# 04_AudioCodec.net
KiCad netlist of a schematic drawn in Altium Designer
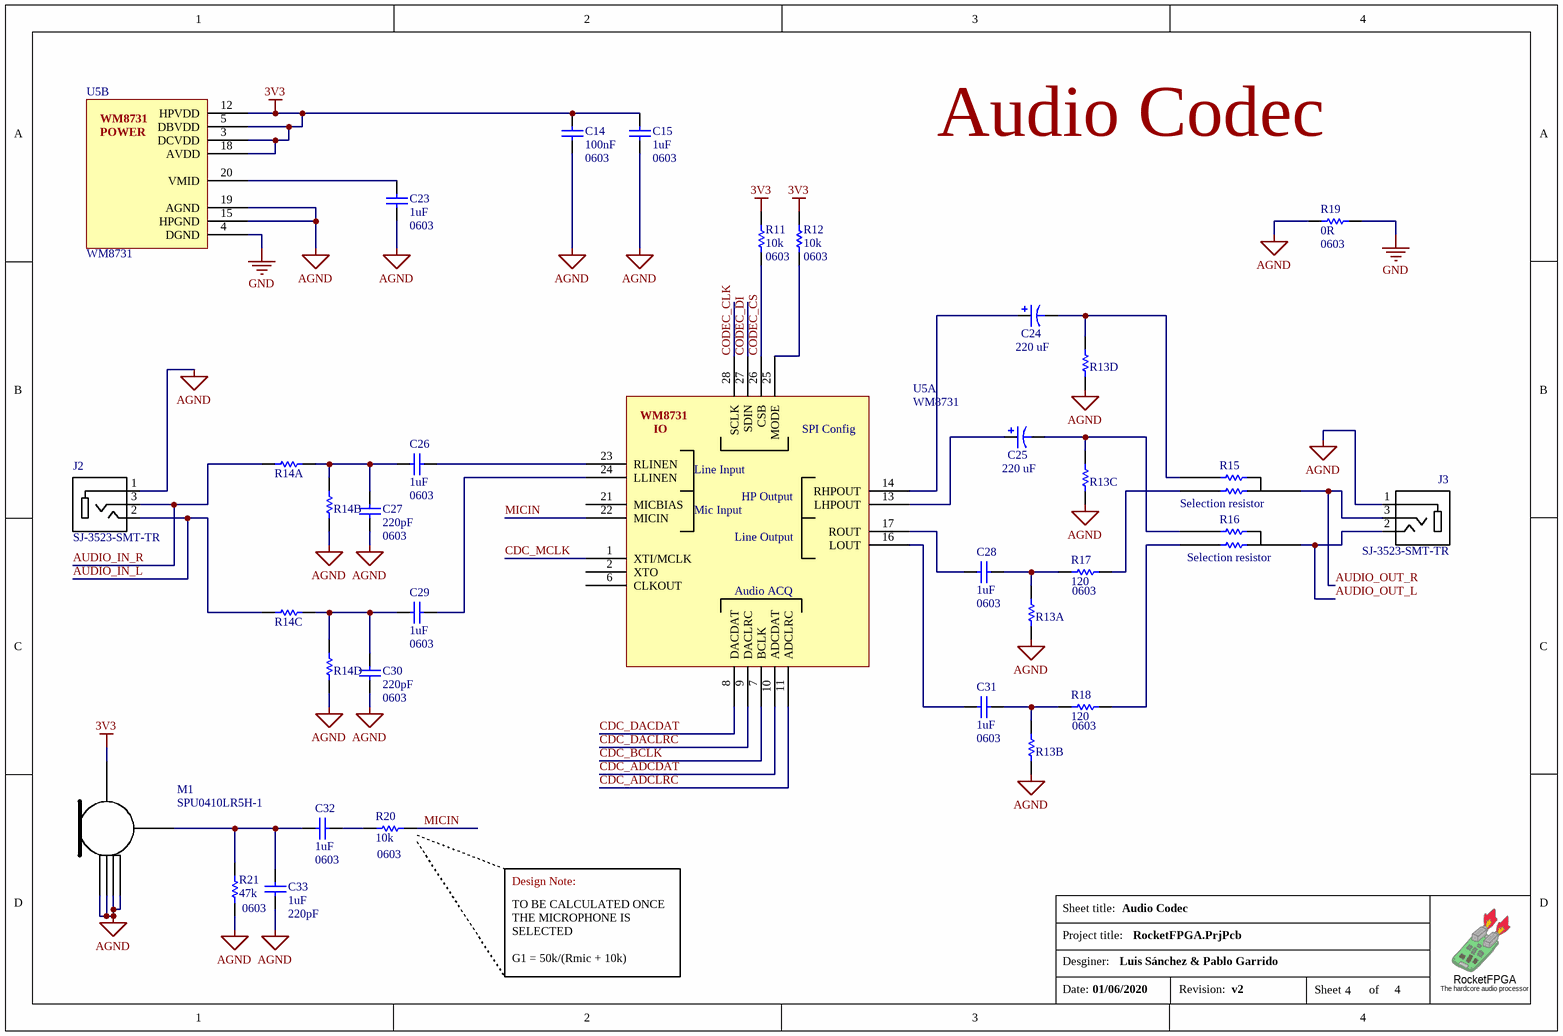
[diagram p0: 04_AudioCodec.SchDoc]

(export (version "E")
  (design (tool "Eeschema 10.0.6"))
  (components
    (comp (ref "C14")
      (value "100nF")
      (footprint "0603 CAP")
      (description "Capacitor")
      (fields (field (name "PACKAGE") "0603") (field (name "Comment") "Ceramic capacitor"))
      (libsource (lib "RocketFPGA") (part "Capacitor"))
    )
    (comp (ref "C15")
      (value "1uF")
      (footprint "0603 CAP")
      (description "Capacitor")
      (fields (field (name "PACKAGE") "0603") (field (name "Comment") "Ceramic capacitor"))
      (libsource (lib "RocketFPGA") (part "Capacitor"))
    )
    (comp (ref "C23")
      (value "1uF")
      (footprint "0603 CAP")
      (description "Capacitor")
      (fields (field (name "PACKAGE") "0603") (field (name "Comment") "Ceramic capacitor"))
      (libsource (lib "RocketFPGA") (part "Capacitor"))
    )
    (comp (ref "C24")
      (value "220 uF")
      (footprint "CAPCP3216X16N")
      (description "Capacitor Electrolitic")
      (fields (field (name "AUTHOR") "Jaime Jiménez Ortega"))
      (libsource (lib "RocketFPGA") (part "Capacitor Electrolitic"))
    )
    (comp (ref "C25")
      (value "220 uF")
      (footprint "CAPCP3216X16N")
      (description "Capacitor Electrolitic")
      (fields (field (name "AUTHOR") "Jaime Jiménez Ortega"))
      (libsource (lib "RocketFPGA") (part "Capacitor Electrolitic"))
    )
    (comp (ref "C26")
      (value "1uF")
      (footprint "0603 CAP")
      (description "Capacitor")
      (fields (field (name "PACKAGE") "0603") (field (name "Comment") "Ceramic capacitor"))
      (libsource (lib "RocketFPGA") (part "Capacitor"))
    )
    (comp (ref "C27")
      (value "220pF")
      (footprint "0603 CAP")
      (description "Capacitor")
      (fields (field (name "PACKAGE") "0603") (field (name "Comment") "Ceramic capacitor"))
      (libsource (lib "RocketFPGA") (part "Capacitor"))
    )
    (comp (ref "C28")
      (value "1uF")
      (footprint "0603 CAP")
      (description "Capacitor")
      (fields (field (name "PACKAGE") "0603") (field (name "Comment") "Ceramic capacitor"))
      (libsource (lib "RocketFPGA") (part "Capacitor"))
    )
    (comp (ref "C29")
      (value "1uF")
      (footprint "0603 CAP")
      (description "Capacitor")
      (fields (field (name "PACKAGE") "0603") (field (name "Comment") "Ceramic capacitor"))
      (libsource (lib "RocketFPGA") (part "Capacitor"))
    )
    (comp (ref "C30")
      (value "220pF")
      (footprint "0603 CAP")
      (description "Capacitor")
      (fields (field (name "PACKAGE") "0603") (field (name "Comment") "Ceramic capacitor"))
      (libsource (lib "RocketFPGA") (part "Capacitor"))
    )
    (comp (ref "C31")
      (value "1uF")
      (footprint "0603 CAP")
      (description "Capacitor")
      (fields (field (name "PACKAGE") "0603") (field (name "Comment") "Ceramic capacitor"))
      (libsource (lib "RocketFPGA") (part "Capacitor"))
    )
    (comp (ref "C32")
      (value "1uF")
      (footprint "0603 CAP")
      (description "Capacitor")
      (fields (field (name "PACKAGE") "0603") (field (name "Comment") "Ceramic capacitor"))
      (libsource (lib "RocketFPGA") (part "Capacitor"))
    )
    (comp (ref "C33")
      (value "1uF")
      (footprint "0603 CAP")
      (description "Capacitor")
      (fields (field (name "PACKAGE") "220pF") (field (name "Comment") "Ceramic capacitor"))
      (libsource (lib "RocketFPGA") (part "Capacitor"))
    )
    (comp (ref "J2")
      (value "SJ-3523-SMT-TR")
      (footprint "CUI_SJ-3523-SMT-TR")
      (description "Jack connector")
      (libsource (lib "RocketFPGA") (part "SJ-3523-SMT-TR"))
    )
    (comp (ref "J3")
      (value "SJ-3523-SMT-TR")
      (footprint "CUI_SJ-3523-SMT-TR")
      (libsource (lib "RocketFPGA") (part "SJ-3523-SMT-TR"))
    )
    (comp (ref "M1")
      (value "SPU0410LR5H-1")
      (footprint "SPU0410LR5H-1")
      (description "MEMS Microphone")
      (libsource (lib "RocketFPGA") (part "SPU0410LR5H-1"))
    )
    (comp (ref "R11")
      (value "10k")
      (footprint "Resistencia 0603")
      (description "Resistor")
      (fields (field (name "PACKAGE") "0603"))
      (libsource (lib "RocketFPGA") (part "Resistor"))
    )
    (comp (ref "R12")
      (value "10k")
      (footprint "Resistencia 0603")
      (description "Resistor")
      (fields (field (name "PACKAGE") "0603"))
      (libsource (lib "RocketFPGA") (part "Resistor"))
    )
    (comp (ref "R13")
      (value "Resistor array")
      (description "4 resistors in smd array configuration")
      (libsource (lib "RocketFPGA") (part "ResistorArray_4"))
    )
    (comp (ref "R14")
      (value "Resistor array")
      (description "4 resistors in smd array configuration")
      (libsource (lib "RocketFPGA") (part "ResistorArray_4"))
    )
    (comp (ref "R15") (value "Selection resistor") (libsource (lib "RocketFPGA") (part "SelectionResistor")))
    (comp (ref "R16") (value "Selection resistor") (libsource (lib "RocketFPGA") (part "SelectionResistor")))
    (comp (ref "R17")
      (value "120")
      (footprint "Resistencia 0603")
      (description "Resistor")
      (fields (field (name "PACKAGE") "0603"))
      (libsource (lib "RocketFPGA") (part "Resistor"))
    )
    (comp (ref "R18")
      (value "120")
      (footprint "Resistencia 0603")
      (description "Resistor")
      (fields (field (name "PACKAGE") "0603"))
      (libsource (lib "RocketFPGA") (part "Resistor"))
    )
    (comp (ref "R19")
      (value "0R")
      (footprint "Resistencia 0603")
      (description "Resistor")
      (fields (field (name "PACKAGE") "0603"))
      (libsource (lib "RocketFPGA") (part "Resistor"))
    )
    (comp (ref "R20")
      (value "10k")
      (footprint "Resistencia 0603")
      (description "Resistor")
      (fields (field (name "PACKAGE") "0603"))
      (libsource (lib "RocketFPGA") (part "Resistor"))
    )
    (comp (ref "R21")
      (value "47k")
      (footprint "Resistencia 0603")
      (description "Resistor")
      (fields (field (name "PACKAGE") "0603"))
      (libsource (lib "RocketFPGA") (part "Resistor"))
    )
    (comp (ref "U5")
      (value "WM8731")
      (footprint "WM8731")
      (description "Portable Internet Audio CODEC with Headphone Driver  and Programmable Sample Rates")
      (libsource (lib "RocketFPGA") (part "WM8731"))
    )
  )
  (nets
    (net (code "1") (name "/AUDIO_IN_L") (class "Default")
      (node (ref "J2") (pin "2") (pinfunction "2_2") (pintype "passive"))
      (node (ref "R14") (pin "3") (pinfunction "3_3") (pintype "passive"))
    )
    (net (code "2") (name "/AUDIO_IN_R") (class "Default")
      (node (ref "J2") (pin "3") (pinfunction "3_3") (pintype "passive"))
      (node (ref "R14") (pin "1") (pinfunction "1_1") (pintype "passive"))
    )
    (net (code "3") (name "/AUDIO_OUT_L") (class "Default")
      (node (ref "J3") (pin "2") (pinfunction "2_2") (pintype "passive"))
      (node (ref "R16") (pin "2") (pinfunction "2_2") (pintype "passive"))
    )
    (net (code "4") (name "/AUDIO_OUT_R") (class "Default")
      (node (ref "J3") (pin "3") (pinfunction "3_3") (pintype "passive"))
      (node (ref "R15") (pin "2") (pinfunction "2_2") (pintype "passive"))
    )
    (net (code "5") (name "/CDC_ADCDAT") (class "Default")
      (node (ref "U5") (pin "10") (pinfunction "ADCDAT_10") (pintype "passive"))
    )
    (net (code "6") (name "/CDC_ADCLRC") (class "Default")
      (node (ref "U5") (pin "11") (pinfunction "ADCLRC_11") (pintype "passive"))
    )
    (net (code "7") (name "/CDC_BCLK") (class "Default")
      (node (ref "U5") (pin "7") (pinfunction "BCLK_7") (pintype "passive"))
    )
    (net (code "8") (name "/CDC_DACDAT") (class "Default")
      (node (ref "U5") (pin "8") (pinfunction "DACDAT_8") (pintype "passive"))
    )
    (net (code "9") (name "/CDC_DACLRC") (class "Default")
      (node (ref "U5") (pin "9") (pinfunction "DACLRC_9") (pintype "passive"))
    )
    (net (code "10") (name "/CDC_MCLK") (class "Default")
      (node (ref "U5") (pin "1") (pinfunction "XTI/MCLK_1") (pintype "passive"))
    )
    (net (code "11") (name "/CODEC_CLK") (class "Default")
      (node (ref "U5") (pin "28") (pinfunction "SCLK_28") (pintype "passive"))
    )
    (net (code "12") (name "/CODEC_CS") (class "Default")
      (node (ref "R11") (pin "1") (pinfunction "1_1") (pintype "passive"))
      (node (ref "U5") (pin "26") (pinfunction "CSB_26") (pintype "passive"))
    )
    (net (code "13") (name "/CODEC_DI") (class "Default")
      (node (ref "U5") (pin "27") (pinfunction "SDIN_27") (pintype "passive"))
    )
    (net (code "14") (name "/MICIN") (class "Default")
      (node (ref "R20") (pin "2") (pinfunction "2_2") (pintype "passive"))
      (node (ref "U5") (pin "22") (pinfunction "MICIN_22") (pintype "passive"))
    )
    (net (code "15") (name "3V3") (class "Default")
      (node (ref "C14") (pin "1") (pinfunction "1_1") (pintype "passive"))
      (node (ref "C15") (pin "1") (pinfunction "1_1") (pintype "passive"))
      (node (ref "M1") (pin "4") (pinfunction "4_4") (pintype "passive"))
      (node (ref "R11") (pin "2") (pinfunction "2_2") (pintype "passive"))
      (node (ref "R12") (pin "2") (pinfunction "2_2") (pintype "passive"))
      (node (ref "U5") (pin "12") (pinfunction "HPVDD_12") (pintype "passive"))
      (node (ref "U5") (pin "18") (pinfunction "AVDD_18") (pintype "passive"))
      (node (ref "U5") (pin "3") (pinfunction "DCVDD_3") (pintype "passive"))
      (node (ref "U5") (pin "5") (pinfunction "DBVDD_5") (pintype "passive"))
    )
    (net (code "16") (name "AGND") (class "Default")
      (node (ref "C14") (pin "2") (pinfunction "2_2") (pintype "passive"))
      (node (ref "C15") (pin "2") (pinfunction "2_2") (pintype "passive"))
      (node (ref "C23") (pin "2") (pinfunction "2_2") (pintype "passive"))
      (node (ref "C27") (pin "2") (pinfunction "2_2") (pintype "passive"))
      (node (ref "C30") (pin "2") (pinfunction "2_2") (pintype "passive"))
      (node (ref "C33") (pin "2") (pinfunction "2_2") (pintype "passive"))
      (node (ref "J2") (pin "1") (pinfunction "1_1") (pintype "passive"))
      (node (ref "J3") (pin "1") (pinfunction "1_1") (pintype "passive"))
      (node (ref "M1") (pin "2") (pinfunction "2_2") (pintype "passive"))
      (node (ref "M1") (pin "3") (pinfunction "3_3") (pintype "passive"))
      (node (ref "M1") (pin "5") (pinfunction "5_5") (pintype "passive"))
      (node (ref "M1") (pin "6") (pinfunction "6_6") (pintype "passive"))
      (node (ref "R13") (pin "5") (pinfunction "5_5") (pintype "passive"))
      (node (ref "R13") (pin "6") (pinfunction "6_6") (pintype "passive"))
      (node (ref "R13") (pin "7") (pinfunction "7_7") (pintype "passive"))
      (node (ref "R13") (pin "8") (pinfunction "8_8") (pintype "passive"))
      (node (ref "R14") (pin "2") (pinfunction "2_2") (pintype "passive"))
      (node (ref "R14") (pin "4") (pinfunction "4_4") (pintype "passive"))
      (node (ref "R19") (pin "2") (pinfunction "2_2") (pintype "passive"))
      (node (ref "R21") (pin "1") (pinfunction "1_1") (pintype "passive"))
      (node (ref "U5") (pin "15") (pinfunction "HPGND_15") (pintype "passive"))
      (node (ref "U5") (pin "19") (pinfunction "AGND_19") (pintype "passive"))
    )
    (net (code "17") (name "GND") (class "Default")
      (node (ref "R19") (pin "1") (pinfunction "1_1") (pintype "passive"))
      (node (ref "U5") (pin "4") (pinfunction "DGND_4") (pintype "passive"))
    )
    (net (code "18") (name "Net-(C24-Pad2)") (class "Default")
      (node (ref "C24") (pin "2") (pinfunction "2_2") (pintype "passive"))
      (node (ref "R13") (pin "4") (pinfunction "4_4") (pintype "passive"))
      (node (ref "R15") (pin "1") (pinfunction "1_1") (pintype "passive"))
    )
    (net (code "19") (name "Net-(C25-Pad2)") (class "Default")
      (node (ref "C25") (pin "2") (pinfunction "2_2") (pintype "passive"))
      (node (ref "R13") (pin "3") (pinfunction "3_3") (pintype "passive"))
      (node (ref "R16") (pin "1") (pinfunction "1_1") (pintype "passive"))
    )
    (net (code "20") (name "Net-(C26-Pad1)") (class "Default")
      (node (ref "C26") (pin "1") (pinfunction "1_1") (pintype "passive"))
      (node (ref "C27") (pin "1") (pinfunction "1_1") (pintype "passive"))
      (node (ref "R14") (pin "7") (pinfunction "7_7") (pintype "passive"))
      (node (ref "R14") (pin "8") (pinfunction "8_8") (pintype "passive"))
    )
    (net (code "21") (name "Net-(C28-Pad2)") (class "Default")
      (node (ref "C28") (pin "2") (pinfunction "2_2") (pintype "passive"))
      (node (ref "R13") (pin "1") (pinfunction "1_1") (pintype "passive"))
      (node (ref "R17") (pin "1") (pinfunction "1_1") (pintype "passive"))
    )
    (net (code "22") (name "Net-(C29-Pad2)") (class "Default")
      (node (ref "C29") (pin "2") (pinfunction "2_2") (pintype "passive"))
      (node (ref "C30") (pin "1") (pinfunction "1_1") (pintype "passive"))
      (node (ref "R14") (pin "5") (pinfunction "5_5") (pintype "passive"))
      (node (ref "R14") (pin "6") (pinfunction "6_6") (pintype "passive"))
    )
    (net (code "23") (name "Net-(C31-Pad2)") (class "Default")
      (node (ref "C31") (pin "2") (pinfunction "2_2") (pintype "passive"))
      (node (ref "R13") (pin "2") (pinfunction "2_2") (pintype "passive"))
      (node (ref "R18") (pin "1") (pinfunction "1_1") (pintype "passive"))
    )
    (net (code "24") (name "Net-(C32-Pad1)") (class "Default")
      (node (ref "C32") (pin "1") (pinfunction "1_1") (pintype "passive"))
      (node (ref "R20") (pin "1") (pinfunction "1_1") (pintype "passive"))
    )
    (net (code "25") (name "Net-(C32-Pad2)") (class "Default")
      (node (ref "C32") (pin "2") (pinfunction "2_2") (pintype "passive"))
      (node (ref "C33") (pin "1") (pinfunction "1_1") (pintype "passive"))
      (node (ref "M1") (pin "1") (pinfunction "1_1") (pintype "passive"))
      (node (ref "R21") (pin "2") (pinfunction "2_2") (pintype "passive"))
    )
    (net (code "26") (name "Net-(R15-Pad3)") (class "Default")
      (node (ref "R15") (pin "3") (pinfunction "3_3") (pintype "passive"))
      (node (ref "R17") (pin "2") (pinfunction "2_2") (pintype "passive"))
    )
    (net (code "27") (name "Net-(R16-Pad3)") (class "Default")
      (node (ref "R16") (pin "3") (pinfunction "3_3") (pintype "passive"))
      (node (ref "R18") (pin "2") (pinfunction "2_2") (pintype "passive"))
    )
    (net (code "28") (name "Net-(U5A-LHPOUT)") (class "Default")
      (node (ref "C25") (pin "1") (pinfunction "1_1") (pintype "passive"))
      (node (ref "U5") (pin "13") (pinfunction "LHPOUT_13") (pintype "passive"))
    )
    (net (code "29") (name "Net-(U5A-LLINEN)") (class "Default")
      (node (ref "C29") (pin "1") (pinfunction "1_1") (pintype "passive"))
      (node (ref "U5") (pin "24") (pinfunction "LLINEN_24") (pintype "passive"))
    )
    (net (code "30") (name "Net-(U5A-LOUT)") (class "Default")
      (node (ref "C31") (pin "1") (pinfunction "1_1") (pintype "passive"))
      (node (ref "U5") (pin "16") (pinfunction "LOUT_16") (pintype "passive"))
    )
    (net (code "31") (name "Net-(U5A-MODE)") (class "Default")
      (node (ref "R12") (pin "1") (pinfunction "1_1") (pintype "passive"))
      (node (ref "U5") (pin "25") (pinfunction "MODE_25") (pintype "passive"))
    )
    (net (code "32") (name "Net-(U5A-RHPOUT)") (class "Default")
      (node (ref "C24") (pin "1") (pinfunction "1_1") (pintype "passive"))
      (node (ref "U5") (pin "14") (pinfunction "RHPOUT_14") (pintype "passive"))
    )
    (net (code "33") (name "Net-(U5A-RLINEN)") (class "Default")
      (node (ref "C26") (pin "2") (pinfunction "2_2") (pintype "passive"))
      (node (ref "U5") (pin "23") (pinfunction "RLINEN_23") (pintype "passive"))
    )
    (net (code "34") (name "Net-(U5A-ROUT)") (class "Default")
      (node (ref "C28") (pin "1") (pinfunction "1_1") (pintype "passive"))
      (node (ref "U5") (pin "17") (pinfunction "ROUT_17") (pintype "passive"))
    )
    (net (code "35") (name "Net-(U5B-VMID)") (class "Default")
      (node (ref "C23") (pin "1") (pinfunction "1_1") (pintype "passive"))
      (node (ref "U5") (pin "20") (pinfunction "VMID_20") (pintype "passive"))
    )
    (net (code "36") (name "unconnected-(U5A-CLKOUT-Pad6)") (class "Default")
      (node (ref "U5") (pin "6") (pinfunction "CLKOUT_6") (pintype "passive"))
    )
    (net (code "37") (name "unconnected-(U5A-MICBIAS-Pad21)") (class "Default")
      (node (ref "U5") (pin "21") (pinfunction "MICBIAS_21") (pintype "passive"))
    )
    (net (code "38") (name "unconnected-(U5A-XTO-Pad2)") (class "Default")
      (node (ref "U5") (pin "2") (pinfunction "XTO_2") (pintype "passive"))
    )
  )
)
